# Schematic_v21.net
KiCad netlist of a schematic drawn in EAGLE
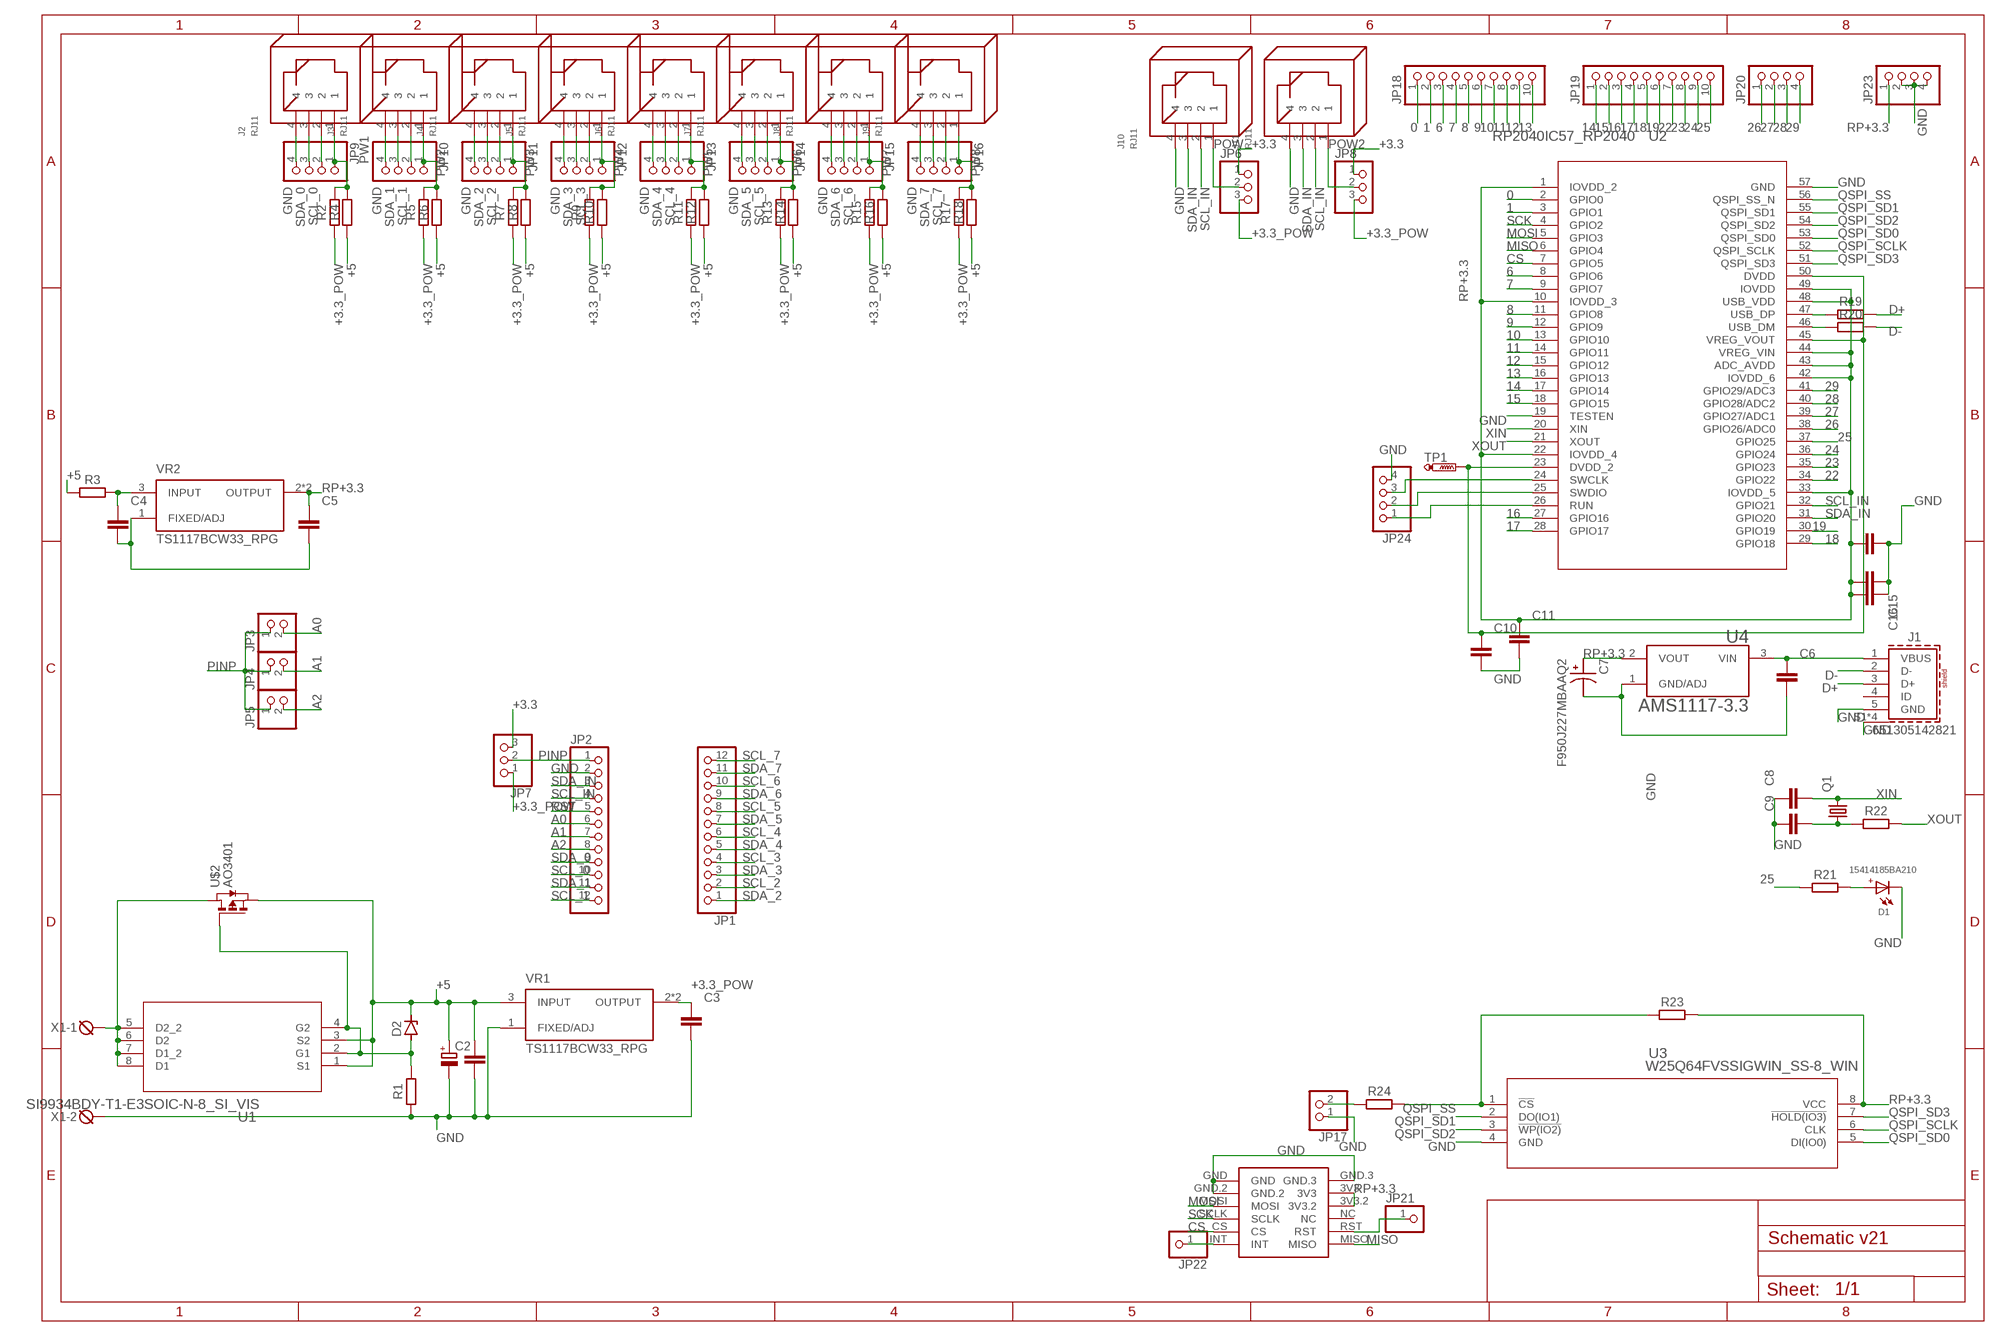
[diagram p0: schematic, sheet 1]

(export (version "E")
  (design (tool "Eeschema 10.0.6"))
  (components
    (comp (ref "C1")
      (value "C_CHIP-0805(2012-METRIC)")
      (footprint "eagle-import:CAPC2012X110")
      (libsource (lib "eagle-import") (part "CCHIP-0805(2012-METRIC)_"))
    )
    (comp (ref "C2")
      (value "C-POL_RADIAL-11MM-DIA")
      (footprint "eagle-import:CAPPRD508W65D1000H1100B")
      (libsource (lib "eagle-import") (part "C-POLRADIAL-11MM-DIA_"))
    )
    (comp (ref "C3")
      (value "C_CHIP-0805(2012-METRIC)")
      (footprint "eagle-import:CAPC2012X110")
      (libsource (lib "eagle-import") (part "CCHIP-0805(2012-METRIC)_"))
    )
    (comp (ref "C4")
      (value "C_CHIP-0805(2012-METRIC)")
      (footprint "eagle-import:CAPC2012X110")
      (libsource (lib "eagle-import") (part "CCHIP-0805(2012-METRIC)_"))
    )
    (comp (ref "C5")
      (value "C_CHIP-0805(2012-METRIC)")
      (footprint "eagle-import:CAPC2012X110")
      (libsource (lib "eagle-import") (part "CCHIP-0805(2012-METRIC)_"))
    )
    (comp (ref "C6")
      (value "C_CHIP-0805(2012-METRIC)")
      (footprint "eagle-import:CAPC2012X110")
      (libsource (lib "eagle-import") (part "CCHIP-0805(2012-METRIC)_"))
    )
    (comp (ref "C7")
      (value "F950J227MBAAQ2")
      (footprint "eagle-import:CAPCP3528X200N")
      (fields (field (name "MF") "KYOCERA AVX"))
      (libsource (lib "eagle-import") (part "F950J227MBAAQ2"))
    )
    (comp (ref "C8")
      (value "C_CHIP-0805(2012-METRIC)")
      (footprint "eagle-import:CAPC2012X110")
      (libsource (lib "eagle-import") (part "CCHIP-0805(2012-METRIC)_"))
    )
    (comp (ref "C9")
      (value "C_CHIP-0805(2012-METRIC)")
      (footprint "eagle-import:CAPC2012X110")
      (libsource (lib "eagle-import") (part "CCHIP-0805(2012-METRIC)_"))
    )
    (comp (ref "C10")
      (value "C_CHIP-0805(2012-METRIC)")
      (footprint "eagle-import:CAPC2012X110")
      (libsource (lib "eagle-import") (part "CCHIP-0805(2012-METRIC)_"))
    )
    (comp (ref "C11")
      (value "C_CHIP-0805(2012-METRIC)")
      (footprint "eagle-import:CAPC2012X110")
      (libsource (lib "eagle-import") (part "CCHIP-0805(2012-METRIC)_"))
    )
    (comp (ref "C12")
      (value "C_CHIP-0805(2012-METRIC)")
      (footprint "eagle-import:CAPC2012X110")
      (libsource (lib "eagle-import") (part "CCHIP-0805(2012-METRIC)_"))
    )
    (comp (ref "C15")
      (value "C_CHIP-0805(2012-METRIC)")
      (footprint "eagle-import:CAPC2012X110")
      (libsource (lib "eagle-import") (part "CCHIP-0805(2012-METRIC)_"))
    )
    (comp (ref "C16")
      (value "C_CHIP-0805(2012-METRIC)")
      (footprint "eagle-import:CAPC2012X110")
      (libsource (lib "eagle-import") (part "CCHIP-0805(2012-METRIC)_"))
    )
    (comp (ref "D1")
      (value "15414185BA210")
      (footprint "eagle-import:WL-SITW_3528")
      (libsource (lib "eagle-import") (part "WL-SITW_3528_15414185BA210"))
    )
    (comp (ref "D2")
      (value "ZENER-DIODESOD80C")
      (footprint "eagle-import:SOD80C")
      (libsource (lib "eagle-import") (part "ZENER-DIODESOD80C"))
    )
    (comp (ref "J1")
      (value "651305142821")
      (footprint "eagle-import:651305142821")
      (libsource (lib "eagle-import") (part "651305142821"))
    )
    (comp (ref "J2")
      (value "RJ11")
      (footprint "eagle-import:RJ11")
      (libsource (lib "eagle-import") (part "RJ11"))
    )
    (comp (ref "J3")
      (value "RJ11")
      (footprint "eagle-import:RJ11")
      (libsource (lib "eagle-import") (part "RJ11"))
    )
    (comp (ref "J4")
      (value "RJ11")
      (footprint "eagle-import:RJ11")
      (libsource (lib "eagle-import") (part "RJ11"))
    )
    (comp (ref "J5")
      (value "RJ11")
      (footprint "eagle-import:RJ11")
      (libsource (lib "eagle-import") (part "RJ11"))
    )
    (comp (ref "J6")
      (value "RJ11")
      (footprint "eagle-import:RJ11")
      (libsource (lib "eagle-import") (part "RJ11"))
    )
    (comp (ref "J7")
      (value "RJ11")
      (footprint "eagle-import:RJ11")
      (libsource (lib "eagle-import") (part "RJ11"))
    )
    (comp (ref "J8")
      (value "RJ11")
      (footprint "eagle-import:RJ11")
      (libsource (lib "eagle-import") (part "RJ11"))
    )
    (comp (ref "J9")
      (value "RJ11")
      (footprint "eagle-import:RJ11")
      (libsource (lib "eagle-import") (part "RJ11"))
    )
    (comp (ref "J10")
      (value "RJ11")
      (footprint "eagle-import:RJ11")
      (libsource (lib "eagle-import") (part "RJ11"))
    )
    (comp (ref "J11")
      (value "RJ11")
      (footprint "eagle-import:RJ11")
      (libsource (lib "eagle-import") (part "RJ11"))
    )
    (comp (ref "JP1")
      (value "PINHD-1X12")
      (footprint "eagle-import:1X12")
      (libsource (lib "eagle-import") (part "PINHD-1X12"))
    )
    (comp (ref "JP2")
      (value "PINHD-1X12")
      (footprint "eagle-import:1X12")
      (libsource (lib "eagle-import") (part "PINHD-1X12"))
    )
    (comp (ref "JP3")
      (value "PINHD-1X2")
      (footprint "eagle-import:1X02")
      (libsource (lib "eagle-import") (part "PINHD-1X2"))
    )
    (comp (ref "JP4")
      (value "PINHD-1X2")
      (footprint "eagle-import:1X02")
      (libsource (lib "eagle-import") (part "PINHD-1X2"))
    )
    (comp (ref "JP5")
      (value "PINHD-1X2")
      (footprint "eagle-import:1X02")
      (libsource (lib "eagle-import") (part "PINHD-1X2"))
    )
    (comp (ref "JP6")
      (value "PINHD-1X3")
      (footprint "eagle-import:1X03")
      (libsource (lib "eagle-import") (part "PINHD-1X3"))
    )
    (comp (ref "JP7")
      (value "PINHD-1X3")
      (footprint "eagle-import:1X03")
      (libsource (lib "eagle-import") (part "PINHD-1X3"))
    )
    (comp (ref "JP8")
      (value "PINHD-1X3")
      (footprint "eagle-import:1X03")
      (libsource (lib "eagle-import") (part "PINHD-1X3"))
    )
    (comp (ref "JP9")
      (value "PINHD-1X4")
      (footprint "eagle-import:1X04")
      (libsource (lib "eagle-import") (part "PINHD-1X4"))
    )
    (comp (ref "JP10")
      (value "PINHD-1X4")
      (footprint "eagle-import:1X04")
      (libsource (lib "eagle-import") (part "PINHD-1X4"))
    )
    (comp (ref "JP11")
      (value "PINHD-1X4")
      (footprint "eagle-import:1X04")
      (libsource (lib "eagle-import") (part "PINHD-1X4"))
    )
    (comp (ref "JP12")
      (value "PINHD-1X4")
      (footprint "eagle-import:1X04")
      (libsource (lib "eagle-import") (part "PINHD-1X4"))
    )
    (comp (ref "JP13")
      (value "PINHD-1X4")
      (footprint "eagle-import:1X04")
      (libsource (lib "eagle-import") (part "PINHD-1X4"))
    )
    (comp (ref "JP14")
      (value "PINHD-1X4")
      (footprint "eagle-import:1X04")
      (libsource (lib "eagle-import") (part "PINHD-1X4"))
    )
    (comp (ref "JP15")
      (value "PINHD-1X4")
      (footprint "eagle-import:1X04")
      (libsource (lib "eagle-import") (part "PINHD-1X4"))
    )
    (comp (ref "JP16")
      (value "PINHD-1X4")
      (footprint "eagle-import:1X04")
      (libsource (lib "eagle-import") (part "PINHD-1X4"))
    )
    (comp (ref "JP17")
      (value "PINHD-1X2")
      (footprint "eagle-import:1X02")
      (libsource (lib "eagle-import") (part "PINHD-1X2"))
    )
    (comp (ref "JP18")
      (value "PINHD-1X10")
      (footprint "eagle-import:1X10")
      (libsource (lib "eagle-import") (part "PINHD-1X10"))
    )
    (comp (ref "JP19")
      (value "PINHD-1X10")
      (footprint "eagle-import:1X10")
      (libsource (lib "eagle-import") (part "PINHD-1X10"))
    )
    (comp (ref "JP20")
      (value "PINHD-1X4")
      (footprint "eagle-import:1X04")
      (libsource (lib "eagle-import") (part "PINHD-1X4"))
    )
    (comp (ref "JP21")
      (value "PINHD-1X1")
      (footprint "eagle-import:1X01")
      (libsource (lib "eagle-import") (part "PINHD-1X1"))
    )
    (comp (ref "JP22")
      (value "PINHD-1X1")
      (footprint "eagle-import:1X01")
      (libsource (lib "eagle-import") (part "PINHD-1X1"))
    )
    (comp (ref "JP23")
      (value "PINHD-1X4")
      (footprint "eagle-import:1X04")
      (libsource (lib "eagle-import") (part "PINHD-1X4"))
    )
    (comp (ref "JP24")
      (value "PINHD-1X4")
      (footprint "eagle-import:1X04")
      (libsource (lib "eagle-import") (part "PINHD-1X4"))
    )
    (comp (ref "Q1")
      (value "KX-9A")
      (footprint "eagle-import:5.0X3.2_KX-9A")
      (libsource (lib "eagle-import") (part "KX-9A"))
    )
    (comp (ref "R1")
      (value "R_AXIAL-7.2MM-PITCH")
      (footprint "eagle-import:RESAD724W46L381D178B")
      (libsource (lib "eagle-import") (part "RAXIAL-7.2MM-PITCH_"))
    )
    (comp (ref "R2")
      (value "R_CHIP-0805(2012-METRIC)")
      (footprint "eagle-import:RESC2012X65")
      (libsource (lib "eagle-import") (part "RCHIP-0805(2012-METRIC)_"))
    )
    (comp (ref "R3")
      (value "R_CHIP-1206(3216-METRIC)")
      (footprint "eagle-import:RESC3216X70")
      (libsource (lib "eagle-import") (part "RCHIP-1206(3216-METRIC)_"))
    )
    (comp (ref "R4")
      (value "R_CHIP-0805(2012-METRIC)")
      (footprint "eagle-import:RESC2012X65")
      (libsource (lib "eagle-import") (part "RCHIP-0805(2012-METRIC)_"))
    )
    (comp (ref "R5")
      (value "R_CHIP-0805(2012-METRIC)")
      (footprint "eagle-import:RESC2012X65")
      (libsource (lib "eagle-import") (part "RCHIP-0805(2012-METRIC)_"))
    )
    (comp (ref "R6")
      (value "R_CHIP-0805(2012-METRIC)")
      (footprint "eagle-import:RESC2012X65")
      (libsource (lib "eagle-import") (part "RCHIP-0805(2012-METRIC)_"))
    )
    (comp (ref "R7")
      (value "R_CHIP-0805(2012-METRIC)")
      (footprint "eagle-import:RESC2012X65")
      (libsource (lib "eagle-import") (part "RCHIP-0805(2012-METRIC)_"))
    )
    (comp (ref "R8")
      (value "R_CHIP-0805(2012-METRIC)")
      (footprint "eagle-import:RESC2012X65")
      (libsource (lib "eagle-import") (part "RCHIP-0805(2012-METRIC)_"))
    )
    (comp (ref "R9")
      (value "R_CHIP-0805(2012-METRIC)")
      (footprint "eagle-import:RESC2012X65")
      (libsource (lib "eagle-import") (part "RCHIP-0805(2012-METRIC)_"))
    )
    (comp (ref "R10")
      (value "R_CHIP-0805(2012-METRIC)")
      (footprint "eagle-import:RESC2012X65")
      (libsource (lib "eagle-import") (part "RCHIP-0805(2012-METRIC)_"))
    )
    (comp (ref "R11")
      (value "R_CHIP-0805(2012-METRIC)")
      (footprint "eagle-import:RESC2012X65")
      (libsource (lib "eagle-import") (part "RCHIP-0805(2012-METRIC)_"))
    )
    (comp (ref "R12")
      (value "R_CHIP-0805(2012-METRIC)")
      (footprint "eagle-import:RESC2012X65")
      (libsource (lib "eagle-import") (part "RCHIP-0805(2012-METRIC)_"))
    )
    (comp (ref "R13")
      (value "R_CHIP-0805(2012-METRIC)")
      (footprint "eagle-import:RESC2012X65")
      (libsource (lib "eagle-import") (part "RCHIP-0805(2012-METRIC)_"))
    )
    (comp (ref "R14")
      (value "R_CHIP-0805(2012-METRIC)")
      (footprint "eagle-import:RESC2012X65")
      (libsource (lib "eagle-import") (part "RCHIP-0805(2012-METRIC)_"))
    )
    (comp (ref "R15")
      (value "R_CHIP-0805(2012-METRIC)")
      (footprint "eagle-import:RESC2012X65")
      (libsource (lib "eagle-import") (part "RCHIP-0805(2012-METRIC)_"))
    )
    (comp (ref "R16")
      (value "R_CHIP-0805(2012-METRIC)")
      (footprint "eagle-import:RESC2012X65")
      (libsource (lib "eagle-import") (part "RCHIP-0805(2012-METRIC)_"))
    )
    (comp (ref "R17")
      (value "R_CHIP-0805(2012-METRIC)")
      (footprint "eagle-import:RESC2012X65")
      (libsource (lib "eagle-import") (part "RCHIP-0805(2012-METRIC)_"))
    )
    (comp (ref "R18")
      (value "R_CHIP-0805(2012-METRIC)")
      (footprint "eagle-import:RESC2012X65")
      (libsource (lib "eagle-import") (part "RCHIP-0805(2012-METRIC)_"))
    )
    (comp (ref "R19")
      (value "R_CHIP-0805(2012-METRIC)")
      (footprint "eagle-import:RESC2012X65")
      (libsource (lib "eagle-import") (part "RCHIP-0805(2012-METRIC)_"))
    )
    (comp (ref "R20")
      (value "R_CHIP-0805(2012-METRIC)")
      (footprint "eagle-import:RESC2012X65")
      (libsource (lib "eagle-import") (part "RCHIP-0805(2012-METRIC)_"))
    )
    (comp (ref "R21")
      (value "R_CHIP-1206(3216-METRIC)")
      (footprint "eagle-import:RESC3216X70")
      (libsource (lib "eagle-import") (part "RCHIP-1206(3216-METRIC)_"))
    )
    (comp (ref "R22")
      (value "R_CHIP-1206(3216-METRIC)")
      (footprint "eagle-import:RESC3216X70")
      (libsource (lib "eagle-import") (part "RCHIP-1206(3216-METRIC)_"))
    )
    (comp (ref "R23")
      (value "R_CHIP-1206(3216-METRIC)")
      (footprint "eagle-import:RESC3216X70")
      (libsource (lib "eagle-import") (part "RCHIP-1206(3216-METRIC)_"))
    )
    (comp (ref "R24")
      (value "R_CHIP-1206(3216-METRIC)")
      (footprint "eagle-import:RESC3216X70")
      (libsource (lib "eagle-import") (part "RCHIP-1206(3216-METRIC)_"))
    )
    (comp (ref "TP1")
      (value "PTR1B1,27")
      (footprint "eagle-import:B1,27")
      (libsource (lib "eagle-import") (part "PTR1B1,27"))
    )
    (comp (ref "U$1")
      (value "MINI_W5500")
      (footprint "eagle-import:MINI_W5500")
      (libsource (lib "eagle-import") (part "MINI_W5500"))
    )
    (comp (ref "U$2")
      (value "AO3401")
      (footprint "eagle-import:SOT23")
      (fields (field (name "MF") "Alpha & Omega Semiconductor"))
      (libsource (lib "eagle-import") (part "AO3401"))
    )
    (comp (ref "U1")
      (value "SI9934BDY-T1-E3SOIC-N-8_SI_VIS")
      (footprint "eagle-import:SOIC-N-8_SI_VIS")
      (fields
        (field (name "MANUFACTURER_PART_NUMBER") "SI9934BDY-T1-E3")
        (field (name "COPYRIGHT") "Copyright (C) 2025 Ultra Librarian. All rights reserved.")
      )
      (libsource (lib "eagle-import") (part "SI9934BDY-T1-E3SOIC-N-8_SI_VIS"))
    )
    (comp (ref "U2")
      (value "RP2040IC57_RP2040")
      (footprint "eagle-import:IC57_RP2040")
      (fields
        (field (name "MANUFACTURER_PART_NUMBER") "RP2040")
        (field (name "COPYRIGHT") "Copyright (C) 2025 Ultra Librarian. All rights reserved.")
      )
      (libsource (lib "eagle-import") (part "RP2040IC57_RP2040"))
    )
    (comp (ref "U3")
      (value "W25Q64FVSSIGWIN_SS-8_WIN")
      (footprint "eagle-import:WIN_SS-8_WIN")
      (fields
        (field (name "MANUFACTURER_PART_NUMBER") "W25Q64FVSSIG")
        (field (name "COPYRIGHT") "Copyright (C) 2025 Ultra Librarian. All rights reserved.")
      )
      (libsource (lib "eagle-import") (part "W25Q64FVSSIGWIN_SS-8_WIN"))
    )
    (comp (ref "U4")
      (value "AMS1117-3.3")
      (footprint "eagle-import:SOT229P700X180-4N")
      (fields (field (name "MF") "ams AG"))
      (libsource (lib "eagle-import") (part "AMS1117-3.3"))
    )
    (comp (ref "VR1")
      (value "TS1117BCW33_RPG")
      (footprint "eagle-import:VREG_TS1117BCW33_RPG")
      (fields (field (name "MF") "Taiwan Semiconductor") (field (name "MP") "TS1117BCW33 RPG"))
      (libsource (lib "eagle-import") (part "TS1117BCW33_RPG"))
    )
    (comp (ref "VR2")
      (value "TS1117BCW33_RPG")
      (footprint "eagle-import:VREG_TS1117BCW33_RPG")
      (fields (field (name "MF") "Taiwan Semiconductor") (field (name "MP") "TS1117BCW33 RPG"))
      (libsource (lib "eagle-import") (part "TS1117BCW33_RPG"))
    )
    (comp (ref "X1")
      (value "DG3XX-02-3.5")
      (footprint "eagle-import:DG350-3.5-02P")
      (libsource (lib "eagle-import") (part "DG3XX-02-3.5"))
    )
  )
  (nets
    (net (code "1") (name "/+3.3") (class "Default")
      (node (ref "JP6") (pin "1") (pinfunction "1_1") (pintype "passive"))
      (node (ref "JP7") (pin "3") (pinfunction "3_3") (pintype "passive"))
      (node (ref "JP8") (pin "1") (pinfunction "1_1") (pintype "passive"))
    )
    (net (code "2") (name "/+3.3_POW") (class "Default")
      (node (ref "C3") (pin "1") (pinfunction "1_1") (pintype "passive"))
      (node (ref "JP6") (pin "3") (pinfunction "3_3") (pintype "passive"))
      (node (ref "JP7") (pin "1") (pinfunction "1_1") (pintype "passive"))
      (node (ref "JP8") (pin "3") (pinfunction "3_3") (pintype "passive"))
      (node (ref "R11") (pin "1") (pinfunction "1_1") (pintype "passive"))
      (node (ref "R13") (pin "1") (pinfunction "1_1") (pintype "passive"))
      (node (ref "R15") (pin "1") (pinfunction "1_1") (pintype "passive"))
      (node (ref "R17") (pin "1") (pinfunction "1_1") (pintype "passive"))
      (node (ref "R2") (pin "1") (pinfunction "1_1") (pintype "passive"))
      (node (ref "R5") (pin "1") (pinfunction "1_1") (pintype "passive"))
      (node (ref "R7") (pin "1") (pinfunction "1_1") (pintype "passive"))
      (node (ref "R9") (pin "1") (pinfunction "1_1") (pintype "passive"))
      (node (ref "VR1") (pin "2") (pinfunction "OUTPUT_2") (pintype "output"))
      (node (ref "VR1") (pin "4") (pinfunction "OUTPUT_4") (pintype "output"))
    )
    (net (code "3") (name "/+5") (class "Default")
      (node (ref "C1") (pin "1") (pinfunction "1_1") (pintype "passive"))
      (node (ref "C2") (pin "1") (pinfunction "+_1") (pintype "passive"))
      (node (ref "D2") (pin "C") (pinfunction "C_C") (pintype "passive"))
      (node (ref "R10") (pin "1") (pinfunction "1_1") (pintype "passive"))
      (node (ref "R12") (pin "1") (pinfunction "1_1") (pintype "passive"))
      (node (ref "R14") (pin "1") (pinfunction "1_1") (pintype "passive"))
      (node (ref "R16") (pin "1") (pinfunction "1_1") (pintype "passive"))
      (node (ref "R18") (pin "1") (pinfunction "1_1") (pintype "passive"))
      (node (ref "R3") (pin "1") (pinfunction "1_1") (pintype "passive"))
      (node (ref "R4") (pin "1") (pinfunction "1_1") (pintype "passive"))
      (node (ref "R6") (pin "1") (pinfunction "1_1") (pintype "passive"))
      (node (ref "R8") (pin "1") (pinfunction "1_1") (pintype "passive"))
      (node (ref "U$2") (pin "2") (pinfunction "S_2") (pintype "passive"))
      (node (ref "U1") (pin "1") (pinfunction "S1_1") (pintype "passive"))
      (node (ref "U1") (pin "3") (pinfunction "S2_3") (pintype "power_in"))
      (node (ref "VR1") (pin "3") (pinfunction "INPUT_3") (pintype "input"))
    )
    (net (code "4") (name "/0") (class "Default")
      (node (ref "JP18") (pin "1") (pinfunction "1_1") (pintype "passive"))
      (node (ref "U2") (pin "2") (pinfunction "GPIO0_2") (pintype "bidirectional"))
    )
    (net (code "5") (name "/1") (class "Default")
      (node (ref "JP18") (pin "2") (pinfunction "2_2") (pintype "passive"))
      (node (ref "U2") (pin "3") (pinfunction "GPIO1_3") (pintype "bidirectional"))
    )
    (net (code "6") (name "/6") (class "Default")
      (node (ref "JP18") (pin "3") (pinfunction "3_3") (pintype "passive"))
      (node (ref "U2") (pin "8") (pinfunction "GPIO6_8") (pintype "bidirectional"))
    )
    (net (code "7") (name "/7") (class "Default")
      (node (ref "JP18") (pin "4") (pinfunction "4_4") (pintype "passive"))
      (node (ref "U2") (pin "9") (pinfunction "GPIO7_9") (pintype "bidirectional"))
    )
    (net (code "8") (name "/8") (class "Default")
      (node (ref "JP18") (pin "5") (pinfunction "5_5") (pintype "passive"))
      (node (ref "U2") (pin "11") (pinfunction "GPIO8_11") (pintype "bidirectional"))
    )
    (net (code "9") (name "/9") (class "Default")
      (node (ref "JP18") (pin "6") (pinfunction "6_6") (pintype "passive"))
      (node (ref "U2") (pin "12") (pinfunction "GPIO9_12") (pintype "bidirectional"))
    )
    (net (code "10") (name "/10") (class "Default")
      (node (ref "JP18") (pin "7") (pinfunction "7_7") (pintype "passive"))
      (node (ref "U2") (pin "13") (pinfunction "GPIO10_13") (pintype "bidirectional"))
    )
    (net (code "11") (name "/11") (class "Default")
      (node (ref "JP18") (pin "8") (pinfunction "8_8") (pintype "passive"))
      (node (ref "U2") (pin "14") (pinfunction "GPIO11_14") (pintype "bidirectional"))
    )
    (net (code "12") (name "/12") (class "Default")
      (node (ref "JP18") (pin "9") (pinfunction "9_9") (pintype "passive"))
      (node (ref "U2") (pin "15") (pinfunction "GPIO12_15") (pintype "bidirectional"))
    )
    (net (code "13") (name "/13") (class "Default")
      (node (ref "JP18") (pin "10") (pinfunction "10_10") (pintype "passive"))
      (node (ref "U2") (pin "16") (pinfunction "GPIO13_16") (pintype "bidirectional"))
    )
    (net (code "14") (name "/14") (class "Default")
      (node (ref "JP19") (pin "1") (pinfunction "1_1") (pintype "passive"))
      (node (ref "U2") (pin "17") (pinfunction "GPIO14_17") (pintype "bidirectional"))
    )
    (net (code "15") (name "/15") (class "Default")
      (node (ref "JP19") (pin "2") (pinfunction "2_2") (pintype "passive"))
      (node (ref "U2") (pin "18") (pinfunction "GPIO15_18") (pintype "bidirectional"))
    )
    (net (code "16") (name "/16") (class "Default")
      (node (ref "JP19") (pin "3") (pinfunction "3_3") (pintype "passive"))
      (node (ref "U2") (pin "27") (pinfunction "GPIO16_27") (pintype "bidirectional"))
    )
    (net (code "17") (name "/17") (class "Default")
      (node (ref "JP19") (pin "4") (pinfunction "4_4") (pintype "passive"))
      (node (ref "U2") (pin "28") (pinfunction "GPIO17_28") (pintype "bidirectional"))
    )
    (net (code "18") (name "/18") (class "Default")
      (node (ref "JP19") (pin "5") (pinfunction "5_5") (pintype "passive"))
      (node (ref "U2") (pin "29") (pinfunction "GPIO18_29") (pintype "bidirectional"))
    )
    (net (code "19") (name "/19") (class "Default")
      (node (ref "JP19") (pin "6") (pinfunction "6_6") (pintype "passive"))
      (node (ref "U2") (pin "30") (pinfunction "GPIO19_30") (pintype "bidirectional"))
    )
    (net (code "20") (name "/22") (class "Default")
      (node (ref "JP19") (pin "7") (pinfunction "7_7") (pintype "passive"))
      (node (ref "U2") (pin "34") (pinfunction "GPIO22_34") (pintype "bidirectional"))
    )
    (net (code "21") (name "/23") (class "Default")
      (node (ref "JP19") (pin "8") (pinfunction "8_8") (pintype "passive"))
      (node (ref "U2") (pin "35") (pinfunction "GPIO23_35") (pintype "bidirectional"))
    )
    (net (code "22") (name "/24") (class "Default")
      (node (ref "JP19") (pin "9") (pinfunction "9_9") (pintype "passive"))
      (node (ref "U2") (pin "36") (pinfunction "GPIO24_36") (pintype "bidirectional"))
    )
    (net (code "23") (name "/25") (class "Default")
      (node (ref "JP19") (pin "10") (pinfunction "10_10") (pintype "passive"))
      (node (ref "R21") (pin "1") (pinfunction "1_1") (pintype "passive"))
      (node (ref "U2") (pin "37") (pinfunction "GPIO25_37") (pintype "bidirectional"))
    )
    (net (code "24") (name "/26") (class "Default")
      (node (ref "JP20") (pin "1") (pinfunction "1_1") (pintype "passive"))
      (node (ref "U2") (pin "38") (pinfunction "GPIO26/ADC0_38") (pintype "bidirectional"))
    )
    (net (code "25") (name "/27") (class "Default")
      (node (ref "JP20") (pin "2") (pinfunction "2_2") (pintype "passive"))
      (node (ref "U2") (pin "39") (pinfunction "GPIO27/ADC1_39") (pintype "bidirectional"))
    )
    (net (code "26") (name "/28") (class "Default")
      (node (ref "JP20") (pin "3") (pinfunction "3_3") (pintype "passive"))
      (node (ref "U2") (pin "40") (pinfunction "GPIO28/ADC2_40") (pintype "bidirectional"))
    )
    (net (code "27") (name "/29") (class "Default")
      (node (ref "JP20") (pin "4") (pinfunction "4_4") (pintype "passive"))
      (node (ref "U2") (pin "41") (pinfunction "GPIO29/ADC3_41") (pintype "bidirectional"))
    )
    (net (code "28") (name "/A0") (class "Default")
      (node (ref "JP2") (pin "6") (pinfunction "6_6") (pintype "passive"))
      (node (ref "JP3") (pin "2") (pinfunction "2_2") (pintype "passive"))
    )
    (net (code "29") (name "/A1") (class "Default")
      (node (ref "JP2") (pin "7") (pinfunction "7_7") (pintype "passive"))
      (node (ref "JP4") (pin "2") (pinfunction "2_2") (pintype "passive"))
    )
    (net (code "30") (name "/A2") (class "Default")
      (node (ref "JP2") (pin "8") (pinfunction "8_8") (pintype "passive"))
      (node (ref "JP5") (pin "2") (pinfunction "2_2") (pintype "passive"))
    )
    (net (code "31") (name "/CS") (class "Default")
      (node (ref "U$1") (pin "CS") (pinfunction "CS_CS") (pintype "bidirectional"))
      (node (ref "U2") (pin "7") (pinfunction "GPIO5_7") (pintype "bidirectional"))
    )
    (net (code "32") (name "/D+") (class "Default")
      (node (ref "J1") (pin "3") (pinfunction "D+_3") (pintype "passive"))
      (node (ref "R19") (pin "2") (pinfunction "2_2") (pintype "passive"))
    )
    (net (code "33") (name "/D-") (class "Default")
      (node (ref "J1") (pin "2") (pinfunction "D-_2") (pintype "passive"))
      (node (ref "R20") (pin "2") (pinfunction "2_2") (pintype "passive"))
    )
    (net (code "34") (name "/GND") (class "Default")
      (node (ref "C1") (pin "2") (pinfunction "2_2") (pintype "passive"))
      (node (ref "C10") (pin "2") (pinfunction "2_2") (pintype "passive"))
      (node (ref "C11") (pin "2") (pinfunction "2_2") (pintype "passive"))
      (node (ref "C12") (pin "1") (pinfunction "1_1") (pintype "passive"))
      (node (ref "C15") (pin "1") (pinfunction "1_1") (pintype "passive"))
      (node (ref "C16") (pin "1") (pinfunction "1_1") (pintype "passive"))
      (node (ref "C2") (pin "2") (pinfunction "-_2") (pintype "passive"))
      (node (ref "C3") (pin "2") (pinfunction "2_2") (pintype "passive"))
      (node (ref "C6") (pin "2") (pinfunction "2_2") (pintype "passive"))
      (node (ref "C7") (pin "2") (pinfunction "2_2") (pintype "passive"))
      (node (ref "C8") (pin "1") (pinfunction "1_1") (pintype "passive"))
      (node (ref "C9") (pin "1") (pinfunction "1_1") (pintype "passive"))
      (node (ref "D1") (pin "2") (pinfunction "-_2") (pintype "passive"))
      (node (ref "J1") (pin "5") (pinfunction "GND_5") (pintype "passive"))
      (node (ref "J1") (pin "S1") (pinfunction "SHIELD_S1") (pintype "passive"))
      (node (ref "J1") (pin "S2") (pinfunction "SHIELD_S2") (pintype "passive"))
      (node (ref "J1") (pin "S3") (pinfunction "SHIELD_S3") (pintype "passive"))
      (node (ref "J1") (pin "S4") (pinfunction "SHIELD_S4") (pintype "passive"))
      (node (ref "J10") (pin "4") (pinfunction "4_4") (pintype "bidirectional"))
      (node (ref "J11") (pin "4") (pinfunction "4_4") (pintype "bidirectional"))
      (node (ref "J2") (pin "4") (pinfunction "4_4") (pintype "bidirectional"))
      (node (ref "J3") (pin "4") (pinfunction "4_4") (pintype "bidirectional"))
      (node (ref "J4") (pin "4") (pinfunction "4_4") (pintype "bidirectional"))
      (node (ref "J5") (pin "4") (pinfunction "4_4") (pintype "bidirectional"))
      (node (ref "J6") (pin "4") (pinfunction "4_4") (pintype "bidirectional"))
      (node (ref "J7") (pin "4") (pinfunction "4_4") (pintype "bidirectional"))
      (node (ref "J8") (pin "4") (pinfunction "4_4") (pintype "bidirectional"))
      (node (ref "J9") (pin "4") (pinfunction "4_4") (pintype "bidirectional"))
      (node (ref "JP10") (pin "4") (pinfunction "4_4") (pintype "passive"))
      (node (ref "JP11") (pin "4") (pinfunction "4_4") (pintype "passive"))
      (node (ref "JP12") (pin "4") (pinfunction "4_4") (pintype "passive"))
      (node (ref "JP13") (pin "4") (pinfunction "4_4") (pintype "passive"))
      (node (ref "JP14") (pin "4") (pinfunction "4_4") (pintype "passive"))
      (node (ref "JP15") (pin "4") (pinfunction "4_4") (pintype "passive"))
      (node (ref "JP16") (pin "4") (pinfunction "4_4") (pintype "passive"))
      (node (ref "JP17") (pin "1") (pinfunction "1_1") (pintype "passive"))
      (node (ref "JP2") (pin "2") (pinfunction "2_2") (pintype "passive"))
      (node (ref "JP23") (pin "2") (pinfunction "2_2") (pintype "passive"))
      (node (ref "JP23") (pin "3") (pinfunction "3_3") (pintype "passive"))
      (node (ref "JP23") (pin "4") (pinfunction "4_4") (pintype "passive"))
      (node (ref "JP24") (pin "4") (pinfunction "4_4") (pintype "passive"))
      (node (ref "JP9") (pin "4") (pinfunction "4_4") (pintype "passive"))
      (node (ref "R1") (pin "1") (pinfunction "1_1") (pintype "passive"))
      (node (ref "U$1") (pin "GND") (pinfunction "GND_GND") (pintype "bidirectional"))
      (node (ref "U$1") (pin "GND.2") (pinfunction "GND.2_GND.2") (pintype "bidirectional"))
      (node (ref "U$1") (pin "GND.3") (pinfunction "GND.3_GND.3") (pintype "bidirectional"))
      (node (ref "U2") (pin "19") (pinfunction "TESTEN_19") (pintype "passive"))
      (node (ref "U2") (pin "57") (pinfunction "GND_57") (pintype "passive"))
      (node (ref "U3") (pin "4") (pinfunction "GND_4") (pintype "power_in"))
      (node (ref "U4") (pin "1") (pinfunction "GND/ADJ_1") (pintype "power_in"))
      (node (ref "VR1") (pin "1") (pinfunction "FIXED/ADJ_1") (pintype "input"))
      (node (ref "X1") (pin "2") (pinfunction "KL_2") (pintype "passive"))
    )
    (net (code "35") (name "/MISO") (class "Default")
      (node (ref "U$1") (pin "MISO") (pinfunction "MISO_MISO") (pintype "bidirectional"))
      (node (ref "U2") (pin "6") (pinfunction "GPIO4_6") (pintype "bidirectional"))
    )
    (net (code "36") (name "/MOSI") (class "Default")
      (node (ref "U$1") (pin "MOSI") (pinfunction "MOSI_MOSI") (pintype "bidirectional"))
      (node (ref "U2") (pin "5") (pinfunction "GPIO3_5") (pintype "bidirectional"))
    )
    (net (code "37") (name "/PINP") (class "Default")
      (node (ref "JP2") (pin "1") (pinfunction "1_1") (pintype "passive"))
      (node (ref "JP3") (pin "1") (pinfunction "1_1") (pintype "passive"))
      (node (ref "JP4") (pin "1") (pinfunction "1_1") (pintype "passive"))
      (node (ref "JP5") (pin "1") (pinfunction "1_1") (pintype "passive"))
      (node (ref "JP7") (pin "2") (pinfunction "2_2") (pintype "passive"))
    )
    (net (code "38") (name "/POW") (class "Default")
      (node (ref "J10") (pin "1") (pinfunction "1_1") (pintype "bidirectional"))
      (node (ref "JP6") (pin "2") (pinfunction "2_2") (pintype "passive"))
    )
    (net (code "39") (name "/POW2") (class "Default")
      (node (ref "J11") (pin "1") (pinfunction "1_1") (pintype "bidirectional"))
      (node (ref "JP8") (pin "2") (pinfunction "2_2") (pintype "passive"))
    )
    (net (code "40") (name "/PW1") (class "Default")
      (node (ref "J2") (pin "1") (pinfunction "1_1") (pintype "bidirectional"))
      (node (ref "JP9") (pin "1") (pinfunction "1_1") (pintype "passive"))
      (node (ref "R2") (pin "2") (pinfunction "2_2") (pintype "passive"))
      (node (ref "R4") (pin "2") (pinfunction "2_2") (pintype "passive"))
    )
    (net (code "41") (name "/PW2") (class "Default")
      (node (ref "J3") (pin "1") (pinfunction "1_1") (pintype "bidirectional"))
      (node (ref "JP10") (pin "1") (pinfunction "1_1") (pintype "passive"))
      (node (ref "R5") (pin "2") (pinfunction "2_2") (pintype "passive"))
      (node (ref "R6") (pin "2") (pinfunction "2_2") (pintype "passive"))
    )
    (net (code "42") (name "/PW3") (class "Default")
      (node (ref "J4") (pin "1") (pinfunction "1_1") (pintype "bidirectional"))
      (node (ref "JP11") (pin "1") (pinfunction "1_1") (pintype "passive"))
      (node (ref "R7") (pin "2") (pinfunction "2_2") (pintype "passive"))
      (node (ref "R8") (pin "2") (pinfunction "2_2") (pintype "passive"))
    )
    (net (code "43") (name "/PW4") (class "Default")
      (node (ref "J5") (pin "1") (pinfunction "1_1") (pintype "bidirectional"))
      (node (ref "JP12") (pin "1") (pinfunction "1_1") (pintype "passive"))
      (node (ref "R10") (pin "2") (pinfunction "2_2") (pintype "passive"))
      (node (ref "R9") (pin "2") (pinfunction "2_2") (pintype "passive"))
    )
    (net (code "44") (name "/PW5") (class "Default")
      (node (ref "J6") (pin "1") (pinfunction "1_1") (pintype "bidirectional"))
      (node (ref "JP13") (pin "1") (pinfunction "1_1") (pintype "passive"))
      (node (ref "R11") (pin "2") (pinfunction "2_2") (pintype "passive"))
      (node (ref "R12") (pin "2") (pinfunction "2_2") (pintype "passive"))
    )
    (net (code "45") (name "/PW6") (class "Default")
      (node (ref "J7") (pin "1") (pinfunction "1_1") (pintype "bidirectional"))
      (node (ref "JP14") (pin "1") (pinfunction "1_1") (pintype "passive"))
      (node (ref "R13") (pin "2") (pinfunction "2_2") (pintype "passive"))
      (node (ref "R14") (pin "2") (pinfunction "2_2") (pintype "passive"))
    )
    (net (code "46") (name "/PW7") (class "Default")
      (node (ref "J8") (pin "1") (pinfunction "1_1") (pintype "bidirectional"))
      (node (ref "JP15") (pin "1") (pinfunction "1_1") (pintype "passive"))
      (node (ref "R15") (pin "2") (pinfunction "2_2") (pintype "passive"))
      (node (ref "R16") (pin "2") (pinfunction "2_2") (pintype "passive"))
    )
    (net (code "47") (name "/PW8") (class "Default")
      (node (ref "J9") (pin "1") (pinfunction "1_1") (pintype "bidirectional"))
      (node (ref "JP16") (pin "1") (pinfunction "1_1") (pintype "passive"))
      (node (ref "R17") (pin "2") (pinfunction "2_2") (pintype "passive"))
      (node (ref "R18") (pin "2") (pinfunction "2_2") (pintype "passive"))
    )
    (net (code "48") (name "/QSPI_SCLK") (class "Default")
      (node (ref "U2") (pin "52") (pinfunction "QSPI_SCLK_52") (pintype "passive"))
      (node (ref "U3") (pin "6") (pinfunction "CLK_6") (pintype "input"))
    )
    (net (code "49") (name "/QSPI_SD0") (class "Default")
      (node (ref "U2") (pin "53") (pinfunction "QSPI_SD0_53") (pintype "bidirectional"))
      (node (ref "U3") (pin "5") (pinfunction "DI(IO0)_5") (pintype "bidirectional"))
    )
    (net (code "50") (name "/QSPI_SD1") (class "Default")
      (node (ref "U2") (pin "55") (pinfunction "QSPI_SD1_55") (pintype "bidirectional"))
      (node (ref "U3") (pin "2") (pinfunction "DO(IO1)_2") (pintype "bidirectional"))
    )
    (net (code "51") (name "/QSPI_SD2") (class "Default")
      (node (ref "U2") (pin "54") (pinfunction "QSPI_SD2_54") (pintype "bidirectional"))
      (node (ref "U3") (pin "3") (pinfunction "~{WP(IO2})_3") (pintype "bidirectional"))
    )
    (net (code "52") (name "/QSPI_SD3") (class "Default")
      (node (ref "U2") (pin "51") (pinfunction "QSPI_SD3_51") (pintype "bidirectional"))
      (node (ref "U3") (pin "7") (pinfunction "~{HOLD(IO3})_7") (pintype "bidirectional"))
    )
    (net (code "53") (name "/QSPI_SS") (class "Default")
      (node (ref "R23") (pin "1") (pinfunction "1_1") (pintype "passive"))
      (node (ref "R24") (pin "2") (pinfunction "2_2") (pintype "passive"))
      (node (ref "U2") (pin "56") (pinfunction "QSPI_SS_N_56") (pintype "passive"))
      (node (ref "U3") (pin "1") (pinfunction "~{CS}_1") (pintype "input"))
    )
    (net (code "54") (name "/RP+3.3") (class "Default")
      (node (ref "C11") (pin "1") (pinfunction "1_1") (pintype "passive"))
      (node (ref "C12") (pin "2") (pinfunction "2_2") (pintype "passive"))
      (node (ref "C15") (pin "2") (pinfunction "2_2") (pintype "passive"))
      (node (ref "C16") (pin "2") (pinfunction "2_2") (pintype "passive"))
      (node (ref "C5") (pin "1") (pinfunction "1_1") (pintype "passive"))
      (node (ref "C7") (pin "1") (pinfunction "1_1") (pintype "passive"))
      (node (ref "JP23") (pin "1") (pinfunction "1_1") (pintype "passive"))
      (node (ref "R23") (pin "2") (pinfunction "2_2") (pintype "passive"))
      (node (ref "U$1") (pin "3V3") (pinfunction "3V3_3V3") (pintype "bidirectional"))
      (node (ref "U$1") (pin "3V3.2") (pinfunction "3V3.2_3V3.2") (pintype "bidirectional"))
      (node (ref "U2") (pin "1") (pinfunction "IOVDD_2_1") (pintype "power_in"))
      (node (ref "U2") (pin "10") (pinfunction "IOVDD_3_10") (pintype "power_in"))
      (node (ref "U2") (pin "22") (pinfunction "IOVDD_4_22") (pintype "power_in"))
      (node (ref "U2") (pin "33") (pinfunction "IOVDD_5_33") (pintype "power_in"))
      (node (ref "U2") (pin "42") (pinfunction "IOVDD_6_42") (pintype "power_in"))
      (node (ref "U2") (pin "43") (pinfunction "ADC_AVDD_43") (pintype "power_in"))
      (node (ref "U2") (pin "44") (pinfunction "VREG_VIN_44") (pintype "passive"))
      (node (ref "U2") (pin "48") (pinfunction "USB_VDD_48") (pintype "power_in"))
      (node (ref "U2") (pin "49") (pinfunction "IOVDD_49") (pintype "power_in"))
      (node (ref "U3") (pin "8") (pinfunction "VCC_8") (pintype "power_in"))
      (node (ref "U4") (pin "2") (pinfunction "VOUT_2") (pintype "output"))
      (node (ref "VR2") (pin "2") (pinfunction "OUTPUT_2") (pintype "output"))
      (node (ref "VR2") (pin "4") (pinfunction "OUTPUT_4") (pintype "output"))
    )
    (net (code "55") (name "/RST") (class "Default")
      (node (ref "JP2") (pin "5") (pinfunction "5_5") (pintype "passive"))
    )
    (net (code "56") (name "/SCK") (class "Default")
      (node (ref "U$1") (pin "SCLK") (pinfunction "SCLK_SCLK") (pintype "bidirectional"))
      (node (ref "U2") (pin "4") (pinfunction "GPIO2_4") (pintype "bidirectional"))
    )
    (net (code "57") (name "/SCL_0") (class "Default")
      (node (ref "J2") (pin "2") (pinfunction "2_2") (pintype "bidirectional"))
      (node (ref "JP2") (pin "10") (pinfunction "10_10") (pintype "passive"))
      (node (ref "JP9") (pin "2") (pinfunction "2_2") (pintype "passive"))
    )
    (net (code "58") (name "/SCL_1") (class "Default")
      (node (ref "J3") (pin "2") (pinfunction "2_2") (pintype "bidirectional"))
      (node (ref "JP10") (pin "2") (pinfunction "2_2") (pintype "passive"))
      (node (ref "JP2") (pin "12") (pinfunction "12_12") (pintype "passive"))
    )
    (net (code "59") (name "/SCL_2") (class "Default")
      (node (ref "J4") (pin "2") (pinfunction "2_2") (pintype "bidirectional"))
      (node (ref "JP1") (pin "2") (pinfunction "2_2") (pintype "passive"))
      (node (ref "JP11") (pin "2") (pinfunction "2_2") (pintype "passive"))
    )
    (net (code "60") (name "/SCL_3") (class "Default")
      (node (ref "J5") (pin "2") (pinfunction "2_2") (pintype "bidirectional"))
      (node (ref "JP1") (pin "4") (pinfunction "4_4") (pintype "passive"))
      (node (ref "JP12") (pin "2") (pinfunction "2_2") (pintype "passive"))
    )
    (net (code "61") (name "/SCL_4") (class "Default")
      (node (ref "J6") (pin "2") (pinfunction "2_2") (pintype "bidirectional"))
      (node (ref "JP1") (pin "6") (pinfunction "6_6") (pintype "passive"))
      (node (ref "JP13") (pin "2") (pinfunction "2_2") (pintype "passive"))
    )
    (net (code "62") (name "/SCL_5") (class "Default")
      (node (ref "J7") (pin "2") (pinfunction "2_2") (pintype "bidirectional"))
      (node (ref "JP1") (pin "8") (pinfunction "8_8") (pintype "passive"))
      (node (ref "JP14") (pin "2") (pinfunction "2_2") (pintype "passive"))
    )
    (net (code "63") (name "/SCL_6") (class "Default")
      (node (ref "J8") (pin "2") (pinfunction "2_2") (pintype "bidirectional"))
      (node (ref "JP1") (pin "10") (pinfunction "10_10") (pintype "passive"))
      (node (ref "JP15") (pin "2") (pinfunction "2_2") (pintype "passive"))
    )
    (net (code "64") (name "/SCL_7") (class "Default")
      (node (ref "J9") (pin "2") (pinfunction "2_2") (pintype "bidirectional"))
      (node (ref "JP1") (pin "12") (pinfunction "12_12") (pintype "passive"))
      (node (ref "JP16") (pin "2") (pinfunction "2_2") (pintype "passive"))
    )
    (net (code "65") (name "/SCL_IN") (class "Default")
      (node (ref "J10") (pin "2") (pinfunction "2_2") (pintype "bidirectional"))
      (node (ref "J11") (pin "2") (pinfunction "2_2") (pintype "bidirectional"))
      (node (ref "JP2") (pin "4") (pinfunction "4_4") (pintype "passive"))
      (node (ref "U2") (pin "32") (pinfunction "GPIO21_32") (pintype "bidirectional"))
    )
    (net (code "66") (name "/SDA_0") (class "Default")
      (node (ref "J2") (pin "3") (pinfunction "3_3") (pintype "bidirectional"))
      (node (ref "JP2") (pin "9") (pinfunction "9_9") (pintype "passive"))
      (node (ref "JP9") (pin "3") (pinfunction "3_3") (pintype "passive"))
    )
    (net (code "67") (name "/SDA_1") (class "Default")
      (node (ref "J3") (pin "3") (pinfunction "3_3") (pintype "bidirectional"))
      (node (ref "JP10") (pin "3") (pinfunction "3_3") (pintype "passive"))
      (node (ref "JP2") (pin "11") (pinfunction "11_11") (pintype "passive"))
    )
    (net (code "68") (name "/SDA_2") (class "Default")
      (node (ref "J4") (pin "3") (pinfunction "3_3") (pintype "bidirectional"))
      (node (ref "JP1") (pin "1") (pinfunction "1_1") (pintype "passive"))
      (node (ref "JP11") (pin "3") (pinfunction "3_3") (pintype "passive"))
    )
    (net (code "69") (name "/SDA_3") (class "Default")
      (node (ref "J5") (pin "3") (pinfunction "3_3") (pintype "bidirectional"))
      (node (ref "JP1") (pin "3") (pinfunction "3_3") (pintype "passive"))
      (node (ref "JP12") (pin "3") (pinfunction "3_3") (pintype "passive"))
    )
    (net (code "70") (name "/SDA_4") (class "Default")
      (node (ref "J6") (pin "3") (pinfunction "3_3") (pintype "bidirectional"))
      (node (ref "JP1") (pin "5") (pinfunction "5_5") (pintype "passive"))
      (node (ref "JP13") (pin "3") (pinfunction "3_3") (pintype "passive"))
    )
    (net (code "71") (name "/SDA_5") (class "Default")
      (node (ref "J7") (pin "3") (pinfunction "3_3") (pintype "bidirectional"))
      (node (ref "JP1") (pin "7") (pinfunction "7_7") (pintype "passive"))
      (node (ref "JP14") (pin "3") (pinfunction "3_3") (pintype "passive"))
    )
    (net (code "72") (name "/SDA_6") (class "Default")
      (node (ref "J8") (pin "3") (pinfunction "3_3") (pintype "bidirectional"))
      (node (ref "JP1") (pin "9") (pinfunction "9_9") (pintype "passive"))
      (node (ref "JP15") (pin "3") (pinfunction "3_3") (pintype "passive"))
    )
    (net (code "73") (name "/SDA_7") (class "Default")
      (node (ref "J9") (pin "3") (pinfunction "3_3") (pintype "bidirectional"))
      (node (ref "JP1") (pin "11") (pinfunction "11_11") (pintype "passive"))
      (node (ref "JP16") (pin "3") (pinfunction "3_3") (pintype "passive"))
    )
    (net (code "74") (name "/SDA_IN") (class "Default")
      (node (ref "J10") (pin "3") (pinfunction "3_3") (pintype "bidirectional"))
      (node (ref "J11") (pin "3") (pinfunction "3_3") (pintype "bidirectional"))
      (node (ref "JP2") (pin "3") (pinfunction "3_3") (pintype "passive"))
      (node (ref "U2") (pin "31") (pinfunction "GPIO20_31") (pintype "bidirectional"))
    )
    (net (code "75") (name "/XIN") (class "Default")
      (node (ref "C8") (pin "2") (pinfunction "2_2") (pintype "passive"))
      (node (ref "Q1") (pin "3") (pinfunction "2_3") (pintype "passive"))
      (node (ref "U2") (pin "20") (pinfunction "XIN_20") (pintype "passive"))
    )
    (net (code "76") (name "/XOUT") (class "Default")
      (node (ref "R22") (pin "2") (pinfunction "2_2") (pintype "passive"))
      (node (ref "U2") (pin "21") (pinfunction "XOUT_21") (pintype "output"))
    )
    (net (code "77") (name "Net-(C9-Pad2)") (class "Default")
      (node (ref "C9") (pin "2") (pinfunction "2_2") (pintype "passive"))
      (node (ref "Q1") (pin "1") (pinfunction "1_1") (pintype "passive"))
      (node (ref "R22") (pin "1") (pinfunction "1_1") (pintype "passive"))
    )
    (net (code "78") (name "Net-(D1-+)") (class "Default")
      (node (ref "D1") (pin "1") (pinfunction "+_1") (pintype "passive"))
      (node (ref "R21") (pin "2") (pinfunction "2_2") (pintype "passive"))
    )
    (net (code "79") (name "Net-(J1-VBUS)") (class "Default")
      (node (ref "C6") (pin "1") (pinfunction "1_1") (pintype "passive"))
      (node (ref "J1") (pin "1") (pinfunction "VBUS_1") (pintype "passive"))
      (node (ref "U4") (pin "3") (pinfunction "VIN_3") (pintype "input"))
    )
    (net (code "80") (name "Net-(JP17-Pad2)") (class "Default")
      (node (ref "JP17") (pin "2") (pinfunction "2_2") (pintype "passive"))
      (node (ref "R24") (pin "1") (pinfunction "1_1") (pintype "passive"))
    )
    (net (code "81") (name "Net-(JP21-Pad1)") (class "Default")
      (node (ref "JP21") (pin "1") (pinfunction "1_1") (pintype "passive"))
      (node (ref "U$1") (pin "RST") (pinfunction "RST_RST") (pintype "bidirectional"))
    )
    (net (code "82") (name "Net-(JP22-Pad1)") (class "Default")
      (node (ref "JP22") (pin "1") (pinfunction "1_1") (pintype "passive"))
      (node (ref "U$1") (pin "INT") (pinfunction "INT_INT") (pintype "bidirectional"))
    )
    (net (code "83") (name "Net-(U$2-D)") (class "Default")
      (node (ref "U$2") (pin "3") (pinfunction "D_3") (pintype "passive"))
      (node (ref "U1") (pin "5") (pinfunction "D2_2_5") (pintype "passive"))
      (node (ref "U1") (pin "6") (pinfunction "D2_6") (pintype "passive"))
      (node (ref "U1") (pin "7") (pinfunction "D1_2_7") (pintype "passive"))
      (node (ref "U1") (pin "8") (pinfunction "D1_8") (pintype "power_in"))
      (node (ref "X1") (pin "1") (pinfunction "KL_1") (pintype "passive"))
    )
    (net (code "84") (name "Net-(U$2-G)") (class "Default")
      (node (ref "D2") (pin "A") (pinfunction "A_A") (pintype "passive"))
      (node (ref "R1") (pin "2") (pinfunction "2_2") (pintype "passive"))
      (node (ref "U$2") (pin "1") (pinfunction "G_1") (pintype "passive"))
      (node (ref "U1") (pin "2") (pinfunction "G1_2") (pintype "power_in"))
      (node (ref "U1") (pin "4") (pinfunction "G2_4") (pintype "passive"))
    )
    (net (code "85") (name "Net-(U2-DVDD)") (class "Default")
      (node (ref "C10") (pin "1") (pinfunction "1_1") (pintype "passive"))
      (node (ref "TP1") (pin "TP") (pinfunction "TP_TP") (pintype "input"))
      (node (ref "U2") (pin "23") (pinfunction "DVDD_2_23") (pintype "power_in"))
      (node (ref "U2") (pin "45") (pinfunction "VREG_VOUT_45") (pintype "output"))
      (node (ref "U2") (pin "50") (pinfunction "DVDD_50") (pintype "power_in"))
    )
    (net (code "86") (name "Net-(U2-RUN)") (class "Default")
      (node (ref "JP24") (pin "1") (pinfunction "1_1") (pintype "passive"))
      (node (ref "U2") (pin "26") (pinfunction "RUN_26") (pintype "passive"))
    )
    (net (code "87") (name "Net-(U2-SWCLK)") (class "Default")
      (node (ref "JP24") (pin "3") (pinfunction "3_3") (pintype "passive"))
      (node (ref "U2") (pin "24") (pinfunction "SWCLK_24") (pintype "passive"))
    )
    (net (code "88") (name "Net-(U2-SWDIO)") (class "Default")
      (node (ref "JP24") (pin "2") (pinfunction "2_2") (pintype "passive"))
      (node (ref "U2") (pin "25") (pinfunction "SWDIO_25") (pintype "passive"))
    )
    (net (code "89") (name "Net-(U2-USB_DM)") (class "Default")
      (node (ref "R20") (pin "1") (pinfunction "1_1") (pintype "passive"))
      (node (ref "U2") (pin "46") (pinfunction "USB_DM_46") (pintype "passive"))
    )
    (net (code "90") (name "Net-(U2-USB_DP)") (class "Default")
      (node (ref "R19") (pin "1") (pinfunction "1_1") (pintype "passive"))
      (node (ref "U2") (pin "47") (pinfunction "USB_DP_47") (pintype "passive"))
    )
    (net (code "91") (name "Net-(VR2-FIXED{slash}ADJ)") (class "Default")
      (node (ref "C4") (pin "2") (pinfunction "2_2") (pintype "passive"))
      (node (ref "C5") (pin "2") (pinfunction "2_2") (pintype "passive"))
      (node (ref "VR2") (pin "1") (pinfunction "FIXED/ADJ_1") (pintype "input"))
    )
    (net (code "92") (name "Net-(VR2-INPUT)") (class "Default")
      (node (ref "C4") (pin "1") (pinfunction "1_1") (pintype "passive"))
      (node (ref "R3") (pin "2") (pinfunction "2_2") (pintype "passive"))
      (node (ref "VR2") (pin "3") (pinfunction "INPUT_3") (pintype "input"))
    )
    (net (code "93") (name "unconnected-(J1-ID-Pad4)") (class "Default")
      (node (ref "J1") (pin "4") (pinfunction "ID_4") (pintype "passive"))
    )
    (net (code "94") (name "unconnected-(U$1-PadNC)") (class "Default")
      (node (ref "U$1") (pin "NC") (pinfunction "NC_NC") (pintype "bidirectional"))
    )
  )
)
